# pardyBuzz.net
KiCad netlist of a schematic drawn in EAGLE
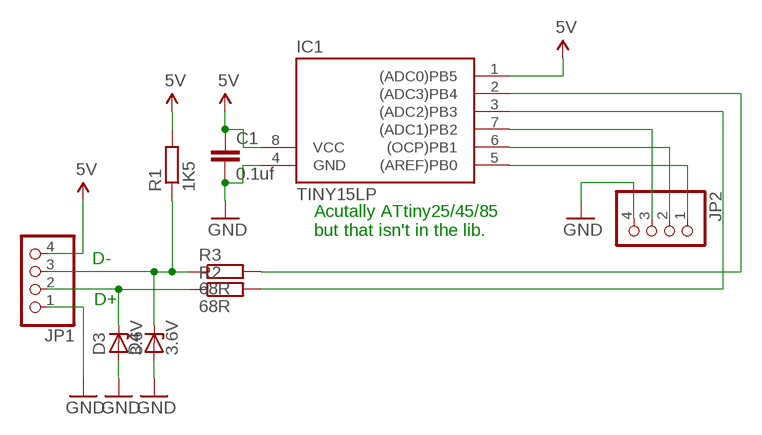
[diagram p0: schematic, sheet 1]

(export (version "E")
  (design (tool "Eeschema 10.0.6"))
  (components
    (comp (ref "C1")
      (value "0.1uf")
      (footprint "eagle-import:C050-024X044")
      (libsource (lib "eagle-import") (part "C-EU050-024X044"))
    )
    (comp (ref "D3")
      (value "3.6V")
      (footprint "eagle-import:DO34Z7")
      (libsource (lib "eagle-import") (part "ZENER-DIODEDO34-7"))
    )
    (comp (ref "D4")
      (value "3.6V")
      (footprint "eagle-import:DO34Z7")
      (libsource (lib "eagle-import") (part "ZENER-DIODEDO34-7"))
    )
    (comp (ref "IC1")
      (value "TINY15LP")
      (footprint "eagle-import:DIL08")
      (libsource (lib "eagle-import") (part "TINY15LP"))
    )
    (comp (ref "JP1")
      (value "PINHD-1X4")
      (footprint "eagle-import:1X04")
      (libsource (lib "eagle-import") (part "PINHD-1X4"))
    )
    (comp (ref "JP2")
      (value "PINHD-1X4")
      (footprint "eagle-import:1X04")
      (libsource (lib "eagle-import") (part "PINHD-1X4"))
    )
    (comp (ref "R1")
      (value "1K5")
      (footprint "eagle-import:0204V")
      (libsource (lib "eagle-import") (part "R-EU_0204/2V"))
    )
    (comp (ref "R2")
      (value "68R")
      (footprint "eagle-import:0204V")
      (libsource (lib "eagle-import") (part "R-EU_0204/2V"))
    )
    (comp (ref "R3")
      (value "68R")
      (footprint "eagle-import:0204V")
      (libsource (lib "eagle-import") (part "R-EU_0204/2V"))
    )
  )
  (nets
    (net (code "1") (name "5V") (class "Default")
      (node (ref "C1") (pin "1") (pinfunction "1_1") (pintype "passive"))
      (node (ref "IC1") (pin "1") (pinfunction "(ADC0)PB5_1") (pintype "bidirectional"))
      (node (ref "IC1") (pin "8") (pinfunction "VCC_8") (pintype "power_in"))
      (node (ref "JP1") (pin "4") (pinfunction "4_4") (pintype "passive"))
      (node (ref "R1") (pin "2") (pinfunction "2_2") (pintype "passive"))
    )
    (net (code "2") (name "GND") (class "Default")
      (node (ref "C1") (pin "2") (pinfunction "2_2") (pintype "passive"))
      (node (ref "D3") (pin "A") (pinfunction "A_A") (pintype "passive"))
      (node (ref "D4") (pin "A") (pinfunction "A_A") (pintype "passive"))
      (node (ref "IC1") (pin "4") (pinfunction "GND_4") (pintype "power_in"))
      (node (ref "JP1") (pin "1") (pinfunction "1_1") (pintype "passive"))
      (node (ref "JP2") (pin "4") (pinfunction "4_4") (pintype "passive"))
    )
    (net (code "3") (name "Net-(D3-PadC)") (class "Default")
      (node (ref "D3") (pin "C") (pinfunction "C_C") (pintype "passive"))
      (node (ref "JP1") (pin "2") (pinfunction "2_2") (pintype "passive"))
      (node (ref "R2") (pin "1") (pinfunction "1_1") (pintype "passive"))
    )
    (net (code "4") (name "Net-(D4-PadC)") (class "Default")
      (node (ref "D4") (pin "C") (pinfunction "C_C") (pintype "passive"))
      (node (ref "JP1") (pin "3") (pinfunction "3_3") (pintype "passive"))
      (node (ref "R1") (pin "1") (pinfunction "1_1") (pintype "passive"))
      (node (ref "R3") (pin "1") (pinfunction "1_1") (pintype "passive"))
    )
    (net (code "5") (name "Net-(IC1-(ADC1)PB2)") (class "Default")
      (node (ref "IC1") (pin "7") (pinfunction "(ADC1)PB2_7") (pintype "bidirectional"))
      (node (ref "JP2") (pin "3") (pinfunction "3_3") (pintype "passive"))
    )
    (net (code "6") (name "Net-(IC1-(ADC2)PB3)") (class "Default")
      (node (ref "IC1") (pin "3") (pinfunction "(ADC2)PB3_3") (pintype "bidirectional"))
      (node (ref "R2") (pin "2") (pinfunction "2_2") (pintype "passive"))
    )
    (net (code "7") (name "Net-(IC1-(ADC3)PB4)") (class "Default")
      (node (ref "IC1") (pin "2") (pinfunction "(ADC3)PB4_2") (pintype "bidirectional"))
      (node (ref "R3") (pin "2") (pinfunction "2_2") (pintype "passive"))
    )
    (net (code "8") (name "Net-(IC1-(AREF)PB0)") (class "Default")
      (node (ref "IC1") (pin "5") (pinfunction "(AREF)PB0_5") (pintype "bidirectional"))
      (node (ref "JP2") (pin "1") (pinfunction "1_1") (pintype "passive"))
    )
    (net (code "9") (name "Net-(IC1-(OCP)PB1)") (class "Default")
      (node (ref "IC1") (pin "6") (pinfunction "(OCP)PB1_6") (pintype "bidirectional"))
      (node (ref "JP2") (pin "2") (pinfunction "2_2") (pintype "passive"))
    )
  )
)
